# XM125.net
KiCad netlist of a schematic drawn in Altium Designer
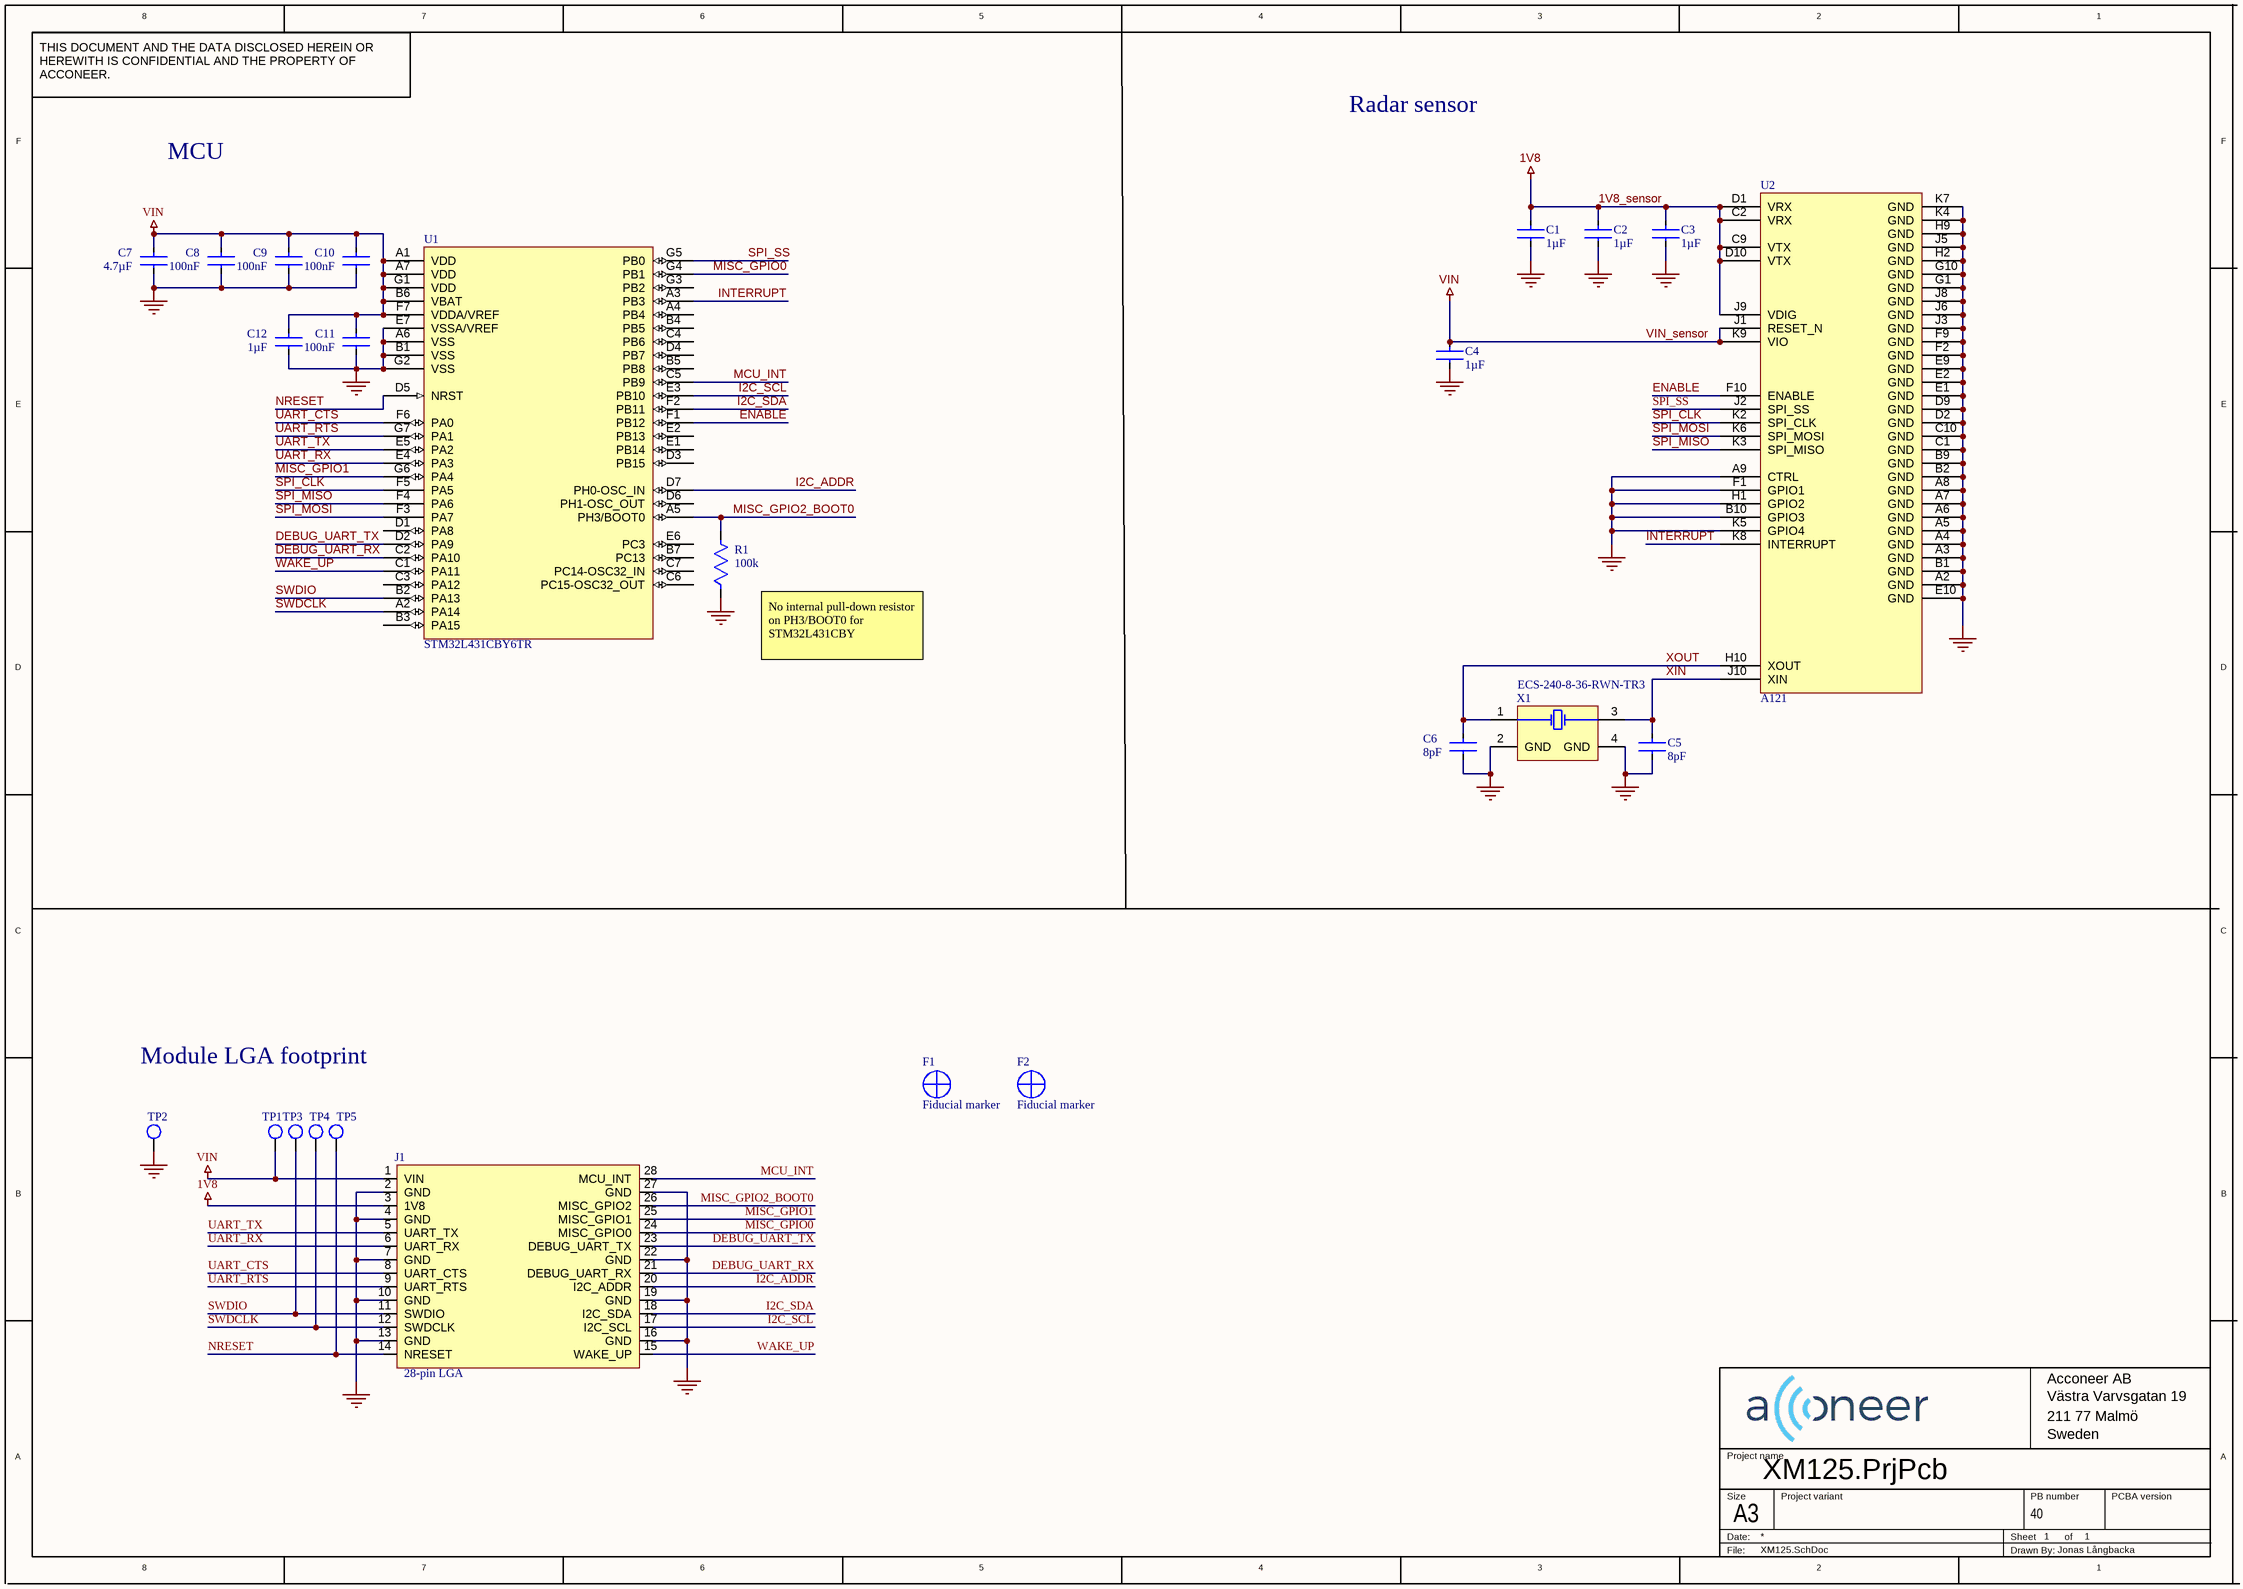
[diagram p0: XM125.SchDoc]

(export (version "E")
  (design (tool "Eeschema 10.0.6"))
  (components
    (comp (ref "C1")
      (value "1µF")
      (footprint "CAPC0603X04L_no_silkscreen")
      (description "Generic 1uF SMD capacitor, metric 0603 (0201)")
      (fields (field (name "TOLERANCE") "20%") (field (name "Comment") "Capacitor 1uF, metric 0603"))
      (libsource (lib "Acconeer AB") (part "Capacitor-Symbol-1"))
    )
    (comp (ref "C2")
      (value "1µF")
      (footprint "CAPC0603X04L_no_silkscreen")
      (description "Generic 1uF SMD capacitor, metric 0603 (0201)")
      (fields (field (name "TOLERANCE") "20%") (field (name "Comment") "Capacitor 1uF, metric 0603"))
      (libsource (lib "Acconeer AB") (part "Capacitor-Symbol-1"))
    )
    (comp (ref "C3")
      (value "1µF")
      (footprint "CAPC0603X04L_no_silkscreen")
      (description "Generic 1uF SMD capacitor, metric 0603 (0201)")
      (fields (field (name "TOLERANCE") "20%") (field (name "Comment") "Capacitor 1uF, metric 0603"))
      (libsource (lib "Acconeer AB") (part "Capacitor-Symbol-1"))
    )
    (comp (ref "C4")
      (value "1µF")
      (footprint "CAPC0603X04L_no_silkscreen")
      (description "Generic 1uF SMD capacitor, metric 0603 (0201)")
      (fields (field (name "TOLERANCE") "20%") (field (name "Comment") "Capacitor 1uF, metric 0603"))
      (libsource (lib "Acconeer AB") (part "Capacitor-Symbol-1"))
    )
    (comp (ref "C5")
      (value "8pF")
      (footprint "CAPC0603X04L_no_silkscreen")
      (description "Generic 8pF SMD capacitor, metric 0603 (0201)")
      (fields (field (name "TOLERANCE") "20%") (field (name "Comment") "Capacitor 8pF, metric 0603"))
      (libsource (lib "Acconeer AB") (part "Capacitor-Symbol-1"))
    )
    (comp (ref "C6")
      (value "8pF")
      (footprint "CAPC0603X04L_no_silkscreen")
      (description "Generic 8pF SMD capacitor, metric 0603 (0201)")
      (fields (field (name "TOLERANCE") "20%") (field (name "Comment") "Capacitor 8pF, metric 0603"))
      (libsource (lib "Acconeer AB") (part "Capacitor-Symbol-1"))
    )
    (comp (ref "C7")
      (value "4.7µF")
      (footprint "CAPC1005X05L")
      (description "Generic 4.7uF SMD capacitor, metric 1005 (0402)")
      (fields (field (name "TOLERANCE") "20%") (field (name "Comment") "Capacitor 4.7uF, metric 1005"))
      (libsource (lib "Acconeer AB") (part "Capacitor-Symbol-1"))
    )
    (comp (ref "C8")
      (value "100nF")
      (footprint "CAPC0603X04L_no_silkscreen")
      (description "Generic 100 nF SMD capacitor, metric 0603 (0201)")
      (fields (field (name "TOLERANCE") "20%") (field (name "Comment") "Capacitor 100nF, metric 0603"))
      (libsource (lib "Acconeer AB") (part "Capacitor-Symbol-1"))
    )
    (comp (ref "C9")
      (value "100nF")
      (footprint "CAPC0603X04L_no_silkscreen")
      (description "Generic 100 nF SMD capacitor, metric 0603 (0201)")
      (fields (field (name "TOLERANCE") "20%") (field (name "Comment") "Capacitor 100nF, metric 0603"))
      (libsource (lib "Acconeer AB") (part "Capacitor-Symbol-1"))
    )
    (comp (ref "C10")
      (value "100nF")
      (footprint "CAPC0603X04L_no_silkscreen")
      (description "Generic 100 nF SMD capacitor, metric 0603 (0201)")
      (fields (field (name "TOLERANCE") "20%") (field (name "Comment") "Capacitor 100nF, metric 0603"))
      (libsource (lib "Acconeer AB") (part "Capacitor-Symbol-1"))
    )
    (comp (ref "C11")
      (value "100nF")
      (footprint "CAPC0603X04L_no_silkscreen")
      (description "Generic 100 nF SMD capacitor, metric 0603 (0201)")
      (fields (field (name "TOLERANCE") "20%") (field (name "Comment") "Capacitor 100nF, metric 0603"))
      (libsource (lib "Acconeer AB") (part "Capacitor-Symbol-1"))
    )
    (comp (ref "C12")
      (value "1µF")
      (footprint "CAPC0603X04L_no_silkscreen")
      (description "Generic 1uF SMD capacitor, metric 0603 (0201)")
      (fields (field (name "TOLERANCE") "20%") (field (name "Comment") "Capacitor 1uF, metric 0603"))
      (libsource (lib "Acconeer AB") (part "Capacitor-Symbol-1"))
    )
    (comp (ref "F1")
      (value "Fiducial marker")
      (footprint "Fiducial 0.5 mm footprint-1")
      (libsource (lib "Acconeer AB") (part "Fiducial"))
    )
    (comp (ref "F2")
      (value "Fiducial marker")
      (footprint "Fiducial 0.5 mm footprint-1")
      (libsource (lib "Acconeer AB") (part "Fiducial"))
    )
    (comp (ref "J1")
      (value "28-pin LGA")
      (footprint "LCCS127P1500X1800X0-28N")
      (description "28-pin Land Grid Array (LGA), pitch 1.27 mm")
      (libsource (lib "Acconeer AB") (part "28-pin LGA symbol-1"))
    )
    (comp (ref "R1")
      (value "100k")
      (footprint "RESC0603X03L_no_silkscreen")
      (description "100 kOhm generic SMD resistor, +/-1%, metric 0603 (0201)")
      (fields (field (name "TOLERANCE") "1%") (field (name "Comment") "Resistor 100 kOhm, metric 0603"))
      (libsource (lib "Acconeer AB") (part "Resistor-Symbol-1"))
    )
    (comp (ref "TP1")
      (value "Testpoint")
      (footprint "Testpoint_circular_0.8_no_silkscreen")
      (description "Circular test point")
      (libsource (lib "Acconeer AB") (part "TP-symbol-1"))
    )
    (comp (ref "TP2")
      (value "Testpoint")
      (footprint "Testpoint_circular_0.8_no_silkscreen")
      (description "Circular test point")
      (libsource (lib "Acconeer AB") (part "TP-symbol-1"))
    )
    (comp (ref "TP3")
      (value "Testpoint")
      (footprint "Testpoint_circular_0.8_no_silkscreen")
      (description "Circular test point")
      (libsource (lib "Acconeer AB") (part "TP-symbol-1"))
    )
    (comp (ref "TP4")
      (value "Testpoint")
      (footprint "Testpoint_circular_0.8_no_silkscreen")
      (description "Circular test point")
      (libsource (lib "Acconeer AB") (part "TP-symbol-1"))
    )
    (comp (ref "TP5")
      (value "Testpoint")
      (footprint "Testpoint_circular_0.8_no_silkscreen")
      (description "Circular test point")
      (libsource (lib "Acconeer AB") (part "TP-symbol-1"))
    )
    (comp (ref "U1")
      (value "STM32L431CBY6TR")
      (footprint "BGA49C40P7X7_314X313X58")
      (description "RISC Microcontroller, 32-Bit, FLASH, 80MHz, CMOS, PBGA49")
      (libsource (lib "Acconeer AB") (part "STM32L431CXY-Symbol-1"))
    )
    (comp (ref "U2")
      (value "A121")
      (footprint "BGA50C50P10X10_520X550X90")
      (description "Acconeer A121 pulsed coherent 60 GHz radar sensor")
      (fields (field (name "MANUFACTURER") "Acconeer AB"))
      (libsource (lib "Acconeer AB") (part "A121-symbol-1"))
    )
    (comp (ref "X1")
      (value "ECS-240-8-36-RWN-TR3")
      (footprint "ECS-240-8-36-RWN-TR3-Footprint-No-Silk")
      (description "Crystal 24 MHz 2.5 x 2.0 mm 4-SMD")
      (fields (field (name "MANUFACTURER") "ECS Inc."))
      (libsource (lib "Acconeer AB") (part "Crystal 4-pin, symbol-1"))
    )
  )
  (nets
    (net (code "1") (name "/DEBUG_UART_RX") (class "Default")
      (node (ref "J1") (pin "21") (pinfunction "DEBUG_UART_RX_21") (pintype "bidirectional"))
      (node (ref "U1") (pin "C2") (pinfunction "PA10_C2") (pintype "bidirectional"))
    )
    (net (code "2") (name "/DEBUG_UART_TX") (class "Default")
      (node (ref "J1") (pin "23") (pinfunction "DEBUG_UART_TX_23") (pintype "bidirectional"))
      (node (ref "U1") (pin "D2") (pinfunction "PA9_D2") (pintype "bidirectional"))
    )
    (net (code "3") (name "/ENABLE") (class "Default")
      (node (ref "U1") (pin "F1") (pinfunction "PB12_F1") (pintype "bidirectional"))
      (node (ref "U2") (pin "F10") (pinfunction "ENABLE_F10") (pintype "passive"))
    )
    (net (code "4") (name "/I2C_ADDR") (class "Default")
      (node (ref "J1") (pin "20") (pinfunction "I2C_ADDR_20") (pintype "bidirectional"))
      (node (ref "U1") (pin "D7") (pinfunction "PH0-OSC_IN_D7") (pintype "bidirectional"))
    )
    (net (code "5") (name "/I2C_SCL") (class "Default")
      (node (ref "J1") (pin "17") (pinfunction "I2C_SCL_17") (pintype "bidirectional"))
      (node (ref "U1") (pin "E3") (pinfunction "PB10_E3") (pintype "bidirectional"))
    )
    (net (code "6") (name "/I2C_SDA") (class "Default")
      (node (ref "J1") (pin "18") (pinfunction "I2C_SDA_18") (pintype "bidirectional"))
      (node (ref "U1") (pin "F2") (pinfunction "PB11_F2") (pintype "bidirectional"))
    )
    (net (code "7") (name "/INTERRUPT") (class "Default")
      (node (ref "U1") (pin "A3") (pinfunction "PB3_A3") (pintype "bidirectional"))
      (node (ref "U2") (pin "K8") (pinfunction "INTERRUPT_K8") (pintype "passive"))
    )
    (net (code "8") (name "/MCU_INT") (class "Default")
      (node (ref "J1") (pin "28") (pinfunction "MCU_INT_28") (pintype "bidirectional"))
      (node (ref "U1") (pin "C5") (pinfunction "PB9_C5") (pintype "bidirectional"))
    )
    (net (code "9") (name "/MISC_GPIO0") (class "Default")
      (node (ref "J1") (pin "24") (pinfunction "MISC_GPIO0_24") (pintype "bidirectional"))
      (node (ref "U1") (pin "G4") (pinfunction "PB1_G4") (pintype "bidirectional"))
    )
    (net (code "10") (name "/MISC_GPIO1") (class "Default")
      (node (ref "J1") (pin "25") (pinfunction "MISC_GPIO1_25") (pintype "bidirectional"))
      (node (ref "U1") (pin "G6") (pinfunction "PA4_G6") (pintype "bidirectional"))
    )
    (net (code "11") (name "/MISC_GPIO2_BOOT0") (class "Default")
      (node (ref "J1") (pin "26") (pinfunction "MISC_GPIO2_26") (pintype "bidirectional"))
      (node (ref "R1") (pin "2") (pinfunction "2_2") (pintype "passive"))
      (node (ref "U1") (pin "A5") (pinfunction "PH3/BOOT0_A5") (pintype "bidirectional"))
    )
    (net (code "12") (name "/NRESET") (class "Default")
      (node (ref "J1") (pin "14") (pinfunction "NRESET_14") (pintype "bidirectional"))
      (node (ref "TP5") (pin "1") (pinfunction "1_1") (pintype "passive"))
      (node (ref "U1") (pin "D5") (pinfunction "NRST_D5") (pintype "input"))
    )
    (net (code "13") (name "/SPI_CLK") (class "Default")
      (node (ref "U1") (pin "F5") (pinfunction "PA5_F5") (pintype "passive"))
      (node (ref "U2") (pin "K2") (pinfunction "SPI_CLK_K2") (pintype "passive"))
    )
    (net (code "14") (name "/SPI_MISO") (class "Default")
      (node (ref "U1") (pin "F4") (pinfunction "PA6_F4") (pintype "passive"))
      (node (ref "U2") (pin "K3") (pinfunction "SPI_MISO_K3") (pintype "passive"))
    )
    (net (code "15") (name "/SPI_MOSI") (class "Default")
      (node (ref "U1") (pin "F3") (pinfunction "PA7_F3") (pintype "passive"))
      (node (ref "U2") (pin "K6") (pinfunction "SPI_MOSI_K6") (pintype "passive"))
    )
    (net (code "16") (name "/SPI_SS") (class "Default")
      (node (ref "U1") (pin "G5") (pinfunction "PB0_G5") (pintype "bidirectional"))
      (node (ref "U2") (pin "J2") (pinfunction "SPI_SS_J2") (pintype "passive"))
    )
    (net (code "17") (name "/SWDCLK") (class "Default")
      (node (ref "J1") (pin "12") (pinfunction "SWDCLK_12") (pintype "bidirectional"))
      (node (ref "TP4") (pin "1") (pinfunction "1_1") (pintype "passive"))
      (node (ref "U1") (pin "A2") (pinfunction "PA14_A2") (pintype "bidirectional"))
    )
    (net (code "18") (name "/SWDIO") (class "Default")
      (node (ref "J1") (pin "11") (pinfunction "SWDIO_11") (pintype "bidirectional"))
      (node (ref "TP3") (pin "1") (pinfunction "1_1") (pintype "passive"))
      (node (ref "U1") (pin "B2") (pinfunction "PA13_B2") (pintype "bidirectional"))
    )
    (net (code "19") (name "/UART_CTS") (class "Default")
      (node (ref "J1") (pin "8") (pinfunction "UART_CTS_8") (pintype "bidirectional"))
      (node (ref "U1") (pin "F6") (pinfunction "PA0_F6") (pintype "bidirectional"))
    )
    (net (code "20") (name "/UART_RTS") (class "Default")
      (node (ref "J1") (pin "9") (pinfunction "UART_RTS_9") (pintype "bidirectional"))
      (node (ref "U1") (pin "G7") (pinfunction "PA1_G7") (pintype "bidirectional"))
    )
    (net (code "21") (name "/UART_RX") (class "Default")
      (node (ref "J1") (pin "6") (pinfunction "UART_RX_6") (pintype "bidirectional"))
      (node (ref "U1") (pin "E4") (pinfunction "PA3_E4") (pintype "bidirectional"))
    )
    (net (code "22") (name "/UART_TX") (class "Default")
      (node (ref "J1") (pin "5") (pinfunction "UART_TX_5") (pintype "bidirectional"))
      (node (ref "U1") (pin "E5") (pinfunction "PA2_E5") (pintype "bidirectional"))
    )
    (net (code "23") (name "/WAKE_UP") (class "Default")
      (node (ref "J1") (pin "15") (pinfunction "WAKE_UP_15") (pintype "bidirectional"))
      (node (ref "U1") (pin "C1") (pinfunction "PA11_C1") (pintype "bidirectional"))
    )
    (net (code "24") (name "/XIN") (class "Default")
      (node (ref "C5") (pin "1") (pinfunction "1_1") (pintype "passive"))
      (node (ref "U2") (pin "J10") (pinfunction "XIN_J10") (pintype "passive"))
      (node (ref "X1") (pin "3") (pinfunction "X2_3") (pintype "passive"))
    )
    (net (code "25") (name "/XOUT") (class "Default")
      (node (ref "C6") (pin "1") (pinfunction "1_1") (pintype "passive"))
      (node (ref "U2") (pin "H10") (pinfunction "XOUT_H10") (pintype "passive"))
      (node (ref "X1") (pin "1") (pinfunction "X1_1") (pintype "passive"))
    )
    (net (code "26") (name "1V8") (class "Default")
      (node (ref "C1") (pin "1") (pinfunction "1_1") (pintype "passive"))
      (node (ref "C2") (pin "1") (pinfunction "1_1") (pintype "passive"))
      (node (ref "C3") (pin "1") (pinfunction "1_1") (pintype "passive"))
      (node (ref "J1") (pin "3") (pinfunction "1V8_3") (pintype "power_in"))
      (node (ref "U2") (pin "C2") (pinfunction "VRX_C2") (pintype "passive"))
      (node (ref "U2") (pin "C9") (pinfunction "VTX_C9") (pintype "passive"))
      (node (ref "U2") (pin "D1") (pinfunction "VRX_D1") (pintype "passive"))
      (node (ref "U2") (pin "D10") (pinfunction "VTX_D10") (pintype "passive"))
      (node (ref "U2") (pin "J9") (pinfunction "VDIG_J9") (pintype "passive"))
    )
    (net (code "27") (name "GND") (class "Default")
      (node (ref "C1") (pin "2") (pinfunction "2_2") (pintype "passive"))
      (node (ref "C10") (pin "2") (pinfunction "2_2") (pintype "passive"))
      (node (ref "C11") (pin "2") (pinfunction "2_2") (pintype "passive"))
      (node (ref "C12") (pin "2") (pinfunction "2_2") (pintype "passive"))
      (node (ref "C2") (pin "2") (pinfunction "2_2") (pintype "passive"))
      (node (ref "C3") (pin "2") (pinfunction "2_2") (pintype "passive"))
      (node (ref "C4") (pin "2") (pinfunction "2_2") (pintype "passive"))
      (node (ref "C5") (pin "2") (pinfunction "2_2") (pintype "passive"))
      (node (ref "C6") (pin "2") (pinfunction "2_2") (pintype "passive"))
      (node (ref "C7") (pin "2") (pinfunction "2_2") (pintype "passive"))
      (node (ref "C8") (pin "2") (pinfunction "2_2") (pintype "passive"))
      (node (ref "C9") (pin "2") (pinfunction "2_2") (pintype "passive"))
      (node (ref "J1") (pin "10") (pinfunction "GND_10") (pintype "passive"))
      (node (ref "J1") (pin "13") (pinfunction "GND_13") (pintype "passive"))
      (node (ref "J1") (pin "16") (pinfunction "GND_16") (pintype "power_in"))
      (node (ref "J1") (pin "19") (pinfunction "GND_19") (pintype "power_in"))
      (node (ref "J1") (pin "2") (pinfunction "GND_2") (pintype "power_in"))
      (node (ref "J1") (pin "22") (pinfunction "GND_22") (pintype "power_in"))
      (node (ref "J1") (pin "27") (pinfunction "GND_27") (pintype "power_in"))
      (node (ref "J1") (pin "4") (pinfunction "GND_4") (pintype "power_in"))
      (node (ref "J1") (pin "7") (pinfunction "GND_7") (pintype "passive"))
      (node (ref "R1") (pin "1") (pinfunction "1_1") (pintype "passive"))
      (node (ref "TP2") (pin "1") (pinfunction "1_1") (pintype "passive"))
      (node (ref "U1") (pin "A6") (pinfunction "VSS_A6") (pintype "power_in"))
      (node (ref "U1") (pin "B1") (pinfunction "VSS_B1") (pintype "power_in"))
      (node (ref "U1") (pin "E7") (pinfunction "VSSA/VREF_E7") (pintype "power_in"))
      (node (ref "U1") (pin "G2") (pinfunction "VSS_G2") (pintype "power_in"))
      (node (ref "U2") (pin "A2") (pinfunction "GND_A2") (pintype "passive"))
      (node (ref "U2") (pin "A3") (pinfunction "GND_A3") (pintype "passive"))
      (node (ref "U2") (pin "A4") (pinfunction "GND_A4") (pintype "passive"))
      (node (ref "U2") (pin "A5") (pinfunction "GND_A5") (pintype "passive"))
      (node (ref "U2") (pin "A6") (pinfunction "GND_A6") (pintype "passive"))
      (node (ref "U2") (pin "A7") (pinfunction "GND_A7") (pintype "passive"))
      (node (ref "U2") (pin "A8") (pinfunction "GND_A8") (pintype "passive"))
      (node (ref "U2") (pin "A9") (pinfunction "CTRL_A9") (pintype "passive"))
      (node (ref "U2") (pin "B1") (pinfunction "GND_B1") (pintype "passive"))
      (node (ref "U2") (pin "B10") (pinfunction "GPIO3_B10") (pintype "passive"))
      (node (ref "U2") (pin "B2") (pinfunction "GND_B2") (pintype "passive"))
      (node (ref "U2") (pin "B9") (pinfunction "GND_B9") (pintype "passive"))
      (node (ref "U2") (pin "C1") (pinfunction "GND_C1") (pintype "passive"))
      (node (ref "U2") (pin "C10") (pinfunction "GND_C10") (pintype "passive"))
      (node (ref "U2") (pin "D2") (pinfunction "GND_D2") (pintype "passive"))
      (node (ref "U2") (pin "D9") (pinfunction "GND_D9") (pintype "passive"))
      (node (ref "U2") (pin "E1") (pinfunction "GND_E1") (pintype "passive"))
      (node (ref "U2") (pin "E10") (pinfunction "GND_E10") (pintype "passive"))
      (node (ref "U2") (pin "E2") (pinfunction "GND_E2") (pintype "passive"))
      (node (ref "U2") (pin "E9") (pinfunction "GND_E9") (pintype "passive"))
      (node (ref "U2") (pin "F1") (pinfunction "GPIO1_F1") (pintype "passive"))
      (node (ref "U2") (pin "F2") (pinfunction "GND_F2") (pintype "passive"))
      (node (ref "U2") (pin "F9") (pinfunction "GND_F9") (pintype "passive"))
      (node (ref "U2") (pin "G1") (pinfunction "GND_G1") (pintype "passive"))
      (node (ref "U2") (pin "G10") (pinfunction "GND_G10") (pintype "passive"))
      (node (ref "U2") (pin "H1") (pinfunction "GPIO2_H1") (pintype "passive"))
      (node (ref "U2") (pin "H2") (pinfunction "GND_H2") (pintype "passive"))
      (node (ref "U2") (pin "H9") (pinfunction "GND_H9") (pintype "passive"))
      (node (ref "U2") (pin "J3") (pinfunction "GND_J3") (pintype "passive"))
      (node (ref "U2") (pin "J5") (pinfunction "GND_J5") (pintype "passive"))
      (node (ref "U2") (pin "J6") (pinfunction "GND_J6") (pintype "passive"))
      (node (ref "U2") (pin "J8") (pinfunction "GND_J8") (pintype "passive"))
      (node (ref "U2") (pin "K4") (pinfunction "GND_K4") (pintype "passive"))
      (node (ref "U2") (pin "K5") (pinfunction "GPIO4_K5") (pintype "passive"))
      (node (ref "U2") (pin "K7") (pinfunction "GND_K7") (pintype "passive"))
      (node (ref "X1") (pin "2") (pinfunction "GND_2") (pintype "power_in"))
      (node (ref "X1") (pin "4") (pinfunction "GND_4") (pintype "power_in"))
    )
    (net (code "28") (name "VIN") (class "Default")
      (node (ref "C10") (pin "1") (pinfunction "1_1") (pintype "passive"))
      (node (ref "C11") (pin "1") (pinfunction "1_1") (pintype "passive"))
      (node (ref "C12") (pin "1") (pinfunction "1_1") (pintype "passive"))
      (node (ref "C4") (pin "1") (pinfunction "1_1") (pintype "passive"))
      (node (ref "C7") (pin "1") (pinfunction "1_1") (pintype "passive"))
      (node (ref "C8") (pin "1") (pinfunction "1_1") (pintype "passive"))
      (node (ref "C9") (pin "1") (pinfunction "1_1") (pintype "passive"))
      (node (ref "J1") (pin "1") (pinfunction "VIN_1") (pintype "power_in"))
      (node (ref "TP1") (pin "1") (pinfunction "1_1") (pintype "passive"))
      (node (ref "U1") (pin "A1") (pinfunction "VDD_A1") (pintype "power_in"))
      (node (ref "U1") (pin "A7") (pinfunction "VDD_A7") (pintype "power_in"))
      (node (ref "U1") (pin "B6") (pinfunction "VBAT_B6") (pintype "power_in"))
      (node (ref "U1") (pin "F7") (pinfunction "VDDA/VREF_F7") (pintype "power_in"))
      (node (ref "U1") (pin "G1") (pinfunction "VDD_G1") (pintype "power_in"))
      (node (ref "U2") (pin "J1") (pinfunction "RESET_N_J1") (pintype "passive"))
      (node (ref "U2") (pin "K9") (pinfunction "VIO_K9") (pintype "passive"))
    )
    (net (code "29") (name "unconnected-(F1-Pad1)") (class "Default")
      (node (ref "F1") (pin "1") (pinfunction "1_1") (pintype "passive"))
    )
    (net (code "30") (name "unconnected-(F2-Pad1)") (class "Default")
      (node (ref "F2") (pin "1") (pinfunction "1_1") (pintype "passive"))
    )
    (net (code "31") (name "unconnected-(U1-PA8-PadD1)") (class "Default")
      (node (ref "U1") (pin "D1") (pinfunction "PA8_D1") (pintype "bidirectional"))
    )
    (net (code "32") (name "unconnected-(U1-PA12-PadC3)") (class "Default")
      (node (ref "U1") (pin "C3") (pinfunction "PA12_C3") (pintype "bidirectional"))
    )
    (net (code "33") (name "unconnected-(U1-PA15-PadB3)") (class "Default")
      (node (ref "U1") (pin "B3") (pinfunction "PA15_B3") (pintype "bidirectional"))
    )
    (net (code "34") (name "unconnected-(U1-PB2-PadG3)") (class "Default")
      (node (ref "U1") (pin "G3") (pinfunction "PB2_G3") (pintype "bidirectional"))
    )
    (net (code "35") (name "unconnected-(U1-PB4-PadA4)") (class "Default")
      (node (ref "U1") (pin "A4") (pinfunction "PB4_A4") (pintype "bidirectional"))
    )
    (net (code "36") (name "unconnected-(U1-PB5-PadB4)") (class "Default")
      (node (ref "U1") (pin "B4") (pinfunction "PB5_B4") (pintype "bidirectional"))
    )
    (net (code "37") (name "unconnected-(U1-PB6-PadC4)") (class "Default")
      (node (ref "U1") (pin "C4") (pinfunction "PB6_C4") (pintype "bidirectional"))
    )
    (net (code "38") (name "unconnected-(U1-PB7-PadD4)") (class "Default")
      (node (ref "U1") (pin "D4") (pinfunction "PB7_D4") (pintype "bidirectional"))
    )
    (net (code "39") (name "unconnected-(U1-PB8-PadB5)") (class "Default")
      (node (ref "U1") (pin "B5") (pinfunction "PB8_B5") (pintype "bidirectional"))
    )
    (net (code "40") (name "unconnected-(U1-PB13-PadE2)") (class "Default")
      (node (ref "U1") (pin "E2") (pinfunction "PB13_E2") (pintype "bidirectional"))
    )
    (net (code "41") (name "unconnected-(U1-PB14-PadE1)") (class "Default")
      (node (ref "U1") (pin "E1") (pinfunction "PB14_E1") (pintype "bidirectional"))
    )
    (net (code "42") (name "unconnected-(U1-PB15-PadD3)") (class "Default")
      (node (ref "U1") (pin "D3") (pinfunction "PB15_D3") (pintype "bidirectional"))
    )
    (net (code "43") (name "unconnected-(U1-PC3-PadE6)") (class "Default")
      (node (ref "U1") (pin "E6") (pinfunction "PC3_E6") (pintype "bidirectional"))
    )
    (net (code "44") (name "unconnected-(U1-PC13-PadB7)") (class "Default")
      (node (ref "U1") (pin "B7") (pinfunction "PC13_B7") (pintype "bidirectional"))
    )
    (net (code "45") (name "unconnected-(U1-PC14-OSC32_IN-PadC7)") (class "Default")
      (node (ref "U1") (pin "C7") (pinfunction "PC14-OSC32_IN_C7") (pintype "bidirectional"))
    )
    (net (code "46") (name "unconnected-(U1-PC15-OSC32_OUT-PadC6)") (class "Default")
      (node (ref "U1") (pin "C6") (pinfunction "PC15-OSC32_OUT_C6") (pintype "bidirectional"))
    )
    (net (code "47") (name "unconnected-(U1-PH1-OSC_OUT-PadD6)") (class "Default")
      (node (ref "U1") (pin "D6") (pinfunction "PH1-OSC_OUT_D6") (pintype "bidirectional"))
    )
  )
)
